# Microphone.net
KiCad netlist of a schematic drawn in Altium Designer
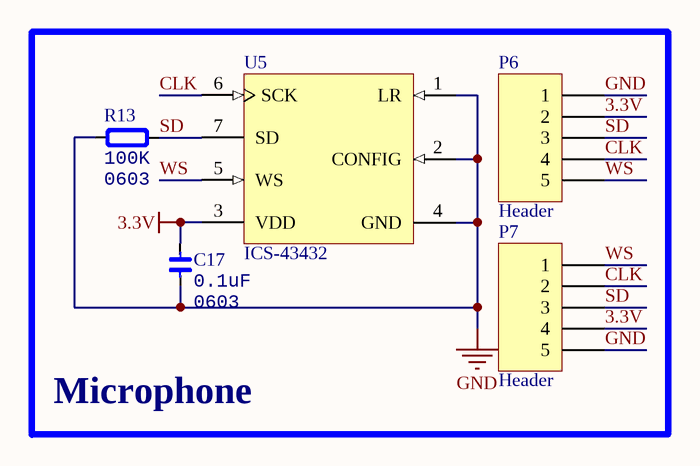
[diagram p0: Microphone.SchDoc]

(export (version "E")
  (design (tool "Eeschema 10.0.6"))
  (components
    (comp (ref "C17")
      (value "0.1uF")
      (footprint "CAP_0603")
      (description "Capacitor SMD")
      (fields
        (field (name "PARTNUMBER") "Capacitor")
        (field (name "CASE/PACKAGE") "0603")
        (field (name "Comment") "C0603")
      )
      (libsource (lib "Integrated_Library") (part "Cap_0603"))
    )
    (comp (ref "P6")
      (value "Header")
      (footprint "ICS-43432 Pin")
      (libsource (lib "Library") (part "ICS-43432 Pin"))
    )
    (comp (ref "P7")
      (value "Header")
      (footprint "ICS-43432 Pin")
      (libsource (lib "Library") (part "ICS-43432 Pin"))
    )
    (comp (ref "R13")
      (value "100K")
      (footprint "RES_0603")
      (description "Resistor SMD")
      (fields
        (field (name "PARTNUMBER") "Resistor")
        (field (name "CASE/PACKAGE") "0603")
        (field (name "Comment") "R0402")
      )
      (libsource (lib "Integrated_Library") (part "Res_0603"))
    )
    (comp (ref "U5")
      (value "ICS-43432")
      (footprint "INSE-ICS-43432_V")
      (description "Low Noise Microphone with I2S Digital Output, 1 mA, -40 to 85 degC, 7-Pin SMD, RoHS, Tape and Reel")
      (fields (field (name "MANUFACTURER") "InvenSense"))
      (libsource (lib "Altium Content Vault") (part "INSE-ICS-43432-7"))
    )
  )
  (nets
    (net (code "1") (name "/CLK") (class "Default")
      (node (ref "P6") (pin "4") (pinfunction "4_4") (pintype "passive"))
      (node (ref "P7") (pin "2") (pinfunction "2_2") (pintype "passive"))
      (node (ref "U5") (pin "6") (pinfunction "SCK_6") (pintype "input"))
    )
    (net (code "2") (name "/SD") (class "Default")
      (node (ref "P6") (pin "3") (pinfunction "3_3") (pintype "passive"))
      (node (ref "P7") (pin "3") (pinfunction "3_3") (pintype "passive"))
      (node (ref "R13") (pin "2") (pinfunction "2_2") (pintype "passive"))
      (node (ref "U5") (pin "7") (pinfunction "SD_7") (pintype "tri_state"))
    )
    (net (code "3") (name "/WS") (class "Default")
      (node (ref "P6") (pin "5") (pinfunction "5_5") (pintype "passive"))
      (node (ref "P7") (pin "1") (pinfunction "1_1") (pintype "passive"))
      (node (ref "U5") (pin "5") (pinfunction "WS_5") (pintype "input"))
    )
    (net (code "4") (name "3.3V") (class "Default")
      (node (ref "C17") (pin "2") (pinfunction "2_2") (pintype "passive"))
      (node (ref "P6") (pin "2") (pinfunction "2_2") (pintype "passive"))
      (node (ref "P7") (pin "4") (pinfunction "4_4") (pintype "passive"))
      (node (ref "U5") (pin "3") (pinfunction "VDD_3") (pintype "power_in"))
    )
    (net (code "5") (name "GND") (class "Default")
      (node (ref "C17") (pin "1") (pinfunction "1_1") (pintype "passive"))
      (node (ref "P6") (pin "1") (pinfunction "1_1") (pintype "passive"))
      (node (ref "P7") (pin "5") (pinfunction "5_5") (pintype "passive"))
      (node (ref "R13") (pin "1") (pinfunction "1_1") (pintype "passive"))
      (node (ref "U5") (pin "1") (pinfunction "LR_1") (pintype "input"))
      (node (ref "U5") (pin "2") (pinfunction "CONFIG_2") (pintype "input"))
      (node (ref "U5") (pin "4") (pinfunction "GND_4") (pintype "power_in"))
    )
  )
)
